# differentialAmp.net
KiCad netlist of a schematic drawn in Altium Designer
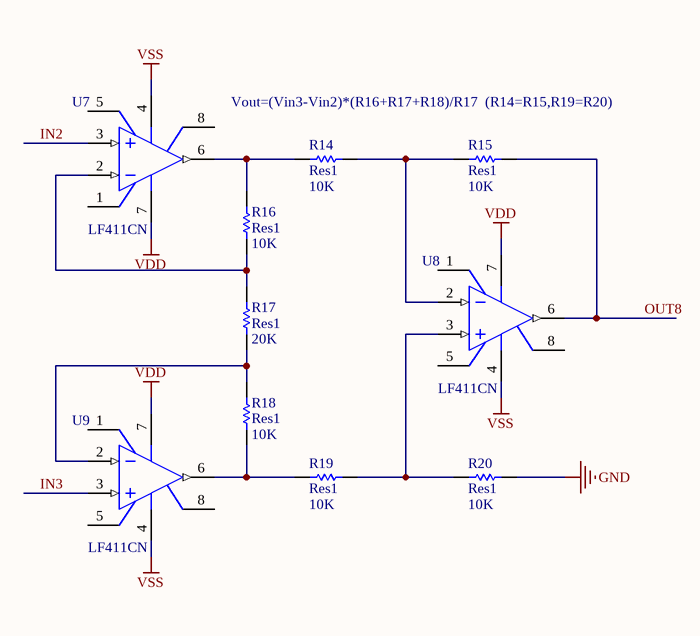
[diagram p0: differentialAmp.SchDoc]

(export (version "E")
  (design (tool "Eeschema 10.0.6"))
  (components
    (comp (ref "R14")
      (value "Res1")
      (footprint "AXIAL-0.3")
      (description "Resistor")
      (fields (field (name "ALTIUM_VALUE") "10K") (field (name "PUBLISHER") "Altium Limited"))
      (libsource (lib "Miscellaneous Devices") (part "Res1"))
    )
    (comp (ref "R15")
      (value "Res1")
      (footprint "AXIAL-0.3")
      (description "Resistor")
      (fields (field (name "ALTIUM_VALUE") "10K") (field (name "PUBLISHER") "Altium Limited"))
      (libsource (lib "Miscellaneous Devices") (part "Res1"))
    )
    (comp (ref "R16")
      (value "Res1")
      (footprint "AXIAL-0.3")
      (description "Resistor")
      (fields (field (name "ALTIUM_VALUE") "10K") (field (name "PUBLISHER") "Altium Limited"))
      (libsource (lib "Miscellaneous Devices") (part "Res1"))
    )
    (comp (ref "R17")
      (value "Res1")
      (footprint "AXIAL-0.3")
      (description "Resistor")
      (fields (field (name "ALTIUM_VALUE") "20K") (field (name "PUBLISHER") "Altium Limited"))
      (libsource (lib "Miscellaneous Devices") (part "Res1"))
    )
    (comp (ref "R18")
      (value "Res1")
      (footprint "AXIAL-0.3")
      (description "Resistor")
      (fields (field (name "ALTIUM_VALUE") "10K") (field (name "PUBLISHER") "Altium Limited"))
      (libsource (lib "Miscellaneous Devices") (part "Res1"))
    )
    (comp (ref "R19")
      (value "Res1")
      (footprint "AXIAL-0.3")
      (description "Resistor")
      (fields (field (name "ALTIUM_VALUE") "10K") (field (name "PUBLISHER") "Altium Limited"))
      (libsource (lib "Miscellaneous Devices") (part "Res1"))
    )
    (comp (ref "R20")
      (value "Res1")
      (footprint "AXIAL-0.3")
      (description "Resistor")
      (fields (field (name "ALTIUM_VALUE") "10K") (field (name "PUBLISHER") "Altium Limited"))
      (libsource (lib "Miscellaneous Devices") (part "Res1"))
    )
    (comp (ref "U7")
      (value "LF411CN")
      (footprint "N08E")
      (description "Low Offset, Low Drift JFET Input Operational Amplifier, 8-pin MDIP")
      (fields
        (field (name "MANUFACTURER") "National Semiconductor")
        (field (name "PUBLISHER") "Altium Limited")
      )
      (libsource (lib "NSC Amplifier") (part "LF411CN"))
    )
    (comp (ref "U8")
      (value "LF411CN")
      (footprint "N08E")
      (description "Low Offset, Low Drift JFET Input Operational Amplifier, 8-pin MDIP")
      (fields
        (field (name "MANUFACTURER") "National Semiconductor")
        (field (name "PUBLISHER") "Altium Limited")
      )
      (libsource (lib "NSC Amplifier") (part "LF411CN"))
    )
    (comp (ref "U9")
      (value "LF411CN")
      (footprint "N08E")
      (description "Low Offset, Low Drift JFET Input Operational Amplifier, 8-pin MDIP")
      (fields
        (field (name "MANUFACTURER") "National Semiconductor")
        (field (name "PUBLISHER") "Altium Limited")
      )
      (libsource (lib "NSC Amplifier") (part "LF411CN"))
    )
  )
  (nets
    (net (code "1") (name "/IN2") (class "Default")
      (node (ref "U7") (pin "3") (pinfunction "IN+_3") (pintype "input"))
    )
    (net (code "2") (name "/IN3") (class "Default")
      (node (ref "U9") (pin "3") (pinfunction "IN+_3") (pintype "input"))
    )
    (net (code "3") (name "/OUT8") (class "Default")
      (node (ref "R15") (pin "2") (pinfunction "2_2") (pintype "passive"))
      (node (ref "U8") (pin "6") (pinfunction "OUT_6") (pintype "output"))
    )
    (net (code "4") (name "GND") (class "Default")
      (node (ref "R20") (pin "2") (pinfunction "2_2") (pintype "passive"))
    )
    (net (code "5") (name "Net-(U7-IN-)") (class "Default")
      (node (ref "R16") (pin "2") (pinfunction "2_2") (pintype "passive"))
      (node (ref "R17") (pin "1") (pinfunction "1_1") (pintype "passive"))
      (node (ref "U7") (pin "2") (pinfunction "IN-_2") (pintype "input"))
    )
    (net (code "6") (name "Net-(U7-OUT)") (class "Default")
      (node (ref "R14") (pin "1") (pinfunction "1_1") (pintype "passive"))
      (node (ref "R16") (pin "1") (pinfunction "1_1") (pintype "passive"))
      (node (ref "U7") (pin "6") (pinfunction "OUT_6") (pintype "output"))
    )
    (net (code "7") (name "Net-(U8-IN+)") (class "Default")
      (node (ref "R19") (pin "2") (pinfunction "2_2") (pintype "passive"))
      (node (ref "R20") (pin "1") (pinfunction "1_1") (pintype "passive"))
      (node (ref "U8") (pin "3") (pinfunction "IN+_3") (pintype "input"))
    )
    (net (code "8") (name "Net-(U8-IN-)") (class "Default")
      (node (ref "R14") (pin "2") (pinfunction "2_2") (pintype "passive"))
      (node (ref "R15") (pin "1") (pinfunction "1_1") (pintype "passive"))
      (node (ref "U8") (pin "2") (pinfunction "IN-_2") (pintype "input"))
    )
    (net (code "9") (name "Net-(U9-IN-)") (class "Default")
      (node (ref "R17") (pin "2") (pinfunction "2_2") (pintype "passive"))
      (node (ref "R18") (pin "1") (pinfunction "1_1") (pintype "passive"))
      (node (ref "U9") (pin "2") (pinfunction "IN-_2") (pintype "input"))
    )
    (net (code "10") (name "Net-(U9-OUT)") (class "Default")
      (node (ref "R18") (pin "2") (pinfunction "2_2") (pintype "passive"))
      (node (ref "R19") (pin "1") (pinfunction "1_1") (pintype "passive"))
      (node (ref "U9") (pin "6") (pinfunction "OUT_6") (pintype "output"))
    )
    (net (code "11") (name "VDD") (class "Default")
      (node (ref "U7") (pin "7") (pinfunction "V+_7") (pintype "power_in"))
      (node (ref "U8") (pin "7") (pinfunction "V+_7") (pintype "power_in"))
      (node (ref "U9") (pin "7") (pinfunction "V+_7") (pintype "power_in"))
    )
    (net (code "12") (name "VSS") (class "Default")
      (node (ref "U7") (pin "4") (pinfunction "V-_4") (pintype "power_in"))
      (node (ref "U8") (pin "4") (pinfunction "V-_4") (pintype "power_in"))
      (node (ref "U9") (pin "4") (pinfunction "V-_4") (pintype "power_in"))
    )
    (net (code "13") (name "unconnected-(U7-BAL-Pad1)") (class "Default")
      (node (ref "U7") (pin "1") (pinfunction "BAL_1") (pintype "passive"))
    )
    (net (code "14") (name "unconnected-(U7-BAL-Pad5)") (class "Default")
      (node (ref "U7") (pin "5") (pinfunction "BAL_5") (pintype "passive"))
    )
    (net (code "15") (name "unconnected-(U7-NC-Pad8)") (class "Default")
      (node (ref "U7") (pin "8") (pinfunction "NC_8") (pintype "passive"))
    )
    (net (code "16") (name "unconnected-(U8-BAL-Pad1)") (class "Default")
      (node (ref "U8") (pin "1") (pinfunction "BAL_1") (pintype "passive"))
    )
    (net (code "17") (name "unconnected-(U8-BAL-Pad5)") (class "Default")
      (node (ref "U8") (pin "5") (pinfunction "BAL_5") (pintype "passive"))
    )
    (net (code "18") (name "unconnected-(U8-NC-Pad8)") (class "Default")
      (node (ref "U8") (pin "8") (pinfunction "NC_8") (pintype "passive"))
    )
    (net (code "19") (name "unconnected-(U9-BAL-Pad1)") (class "Default")
      (node (ref "U9") (pin "1") (pinfunction "BAL_1") (pintype "passive"))
    )
    (net (code "20") (name "unconnected-(U9-BAL-Pad5)") (class "Default")
      (node (ref "U9") (pin "5") (pinfunction "BAL_5") (pintype "passive"))
    )
    (net (code "21") (name "unconnected-(U9-NC-Pad8)") (class "Default")
      (node (ref "U9") (pin "8") (pinfunction "NC_8") (pintype "passive"))
    )
  )
)
